# p6_wch_link.net
KiCad netlist of a schematic drawn in Altium Designer
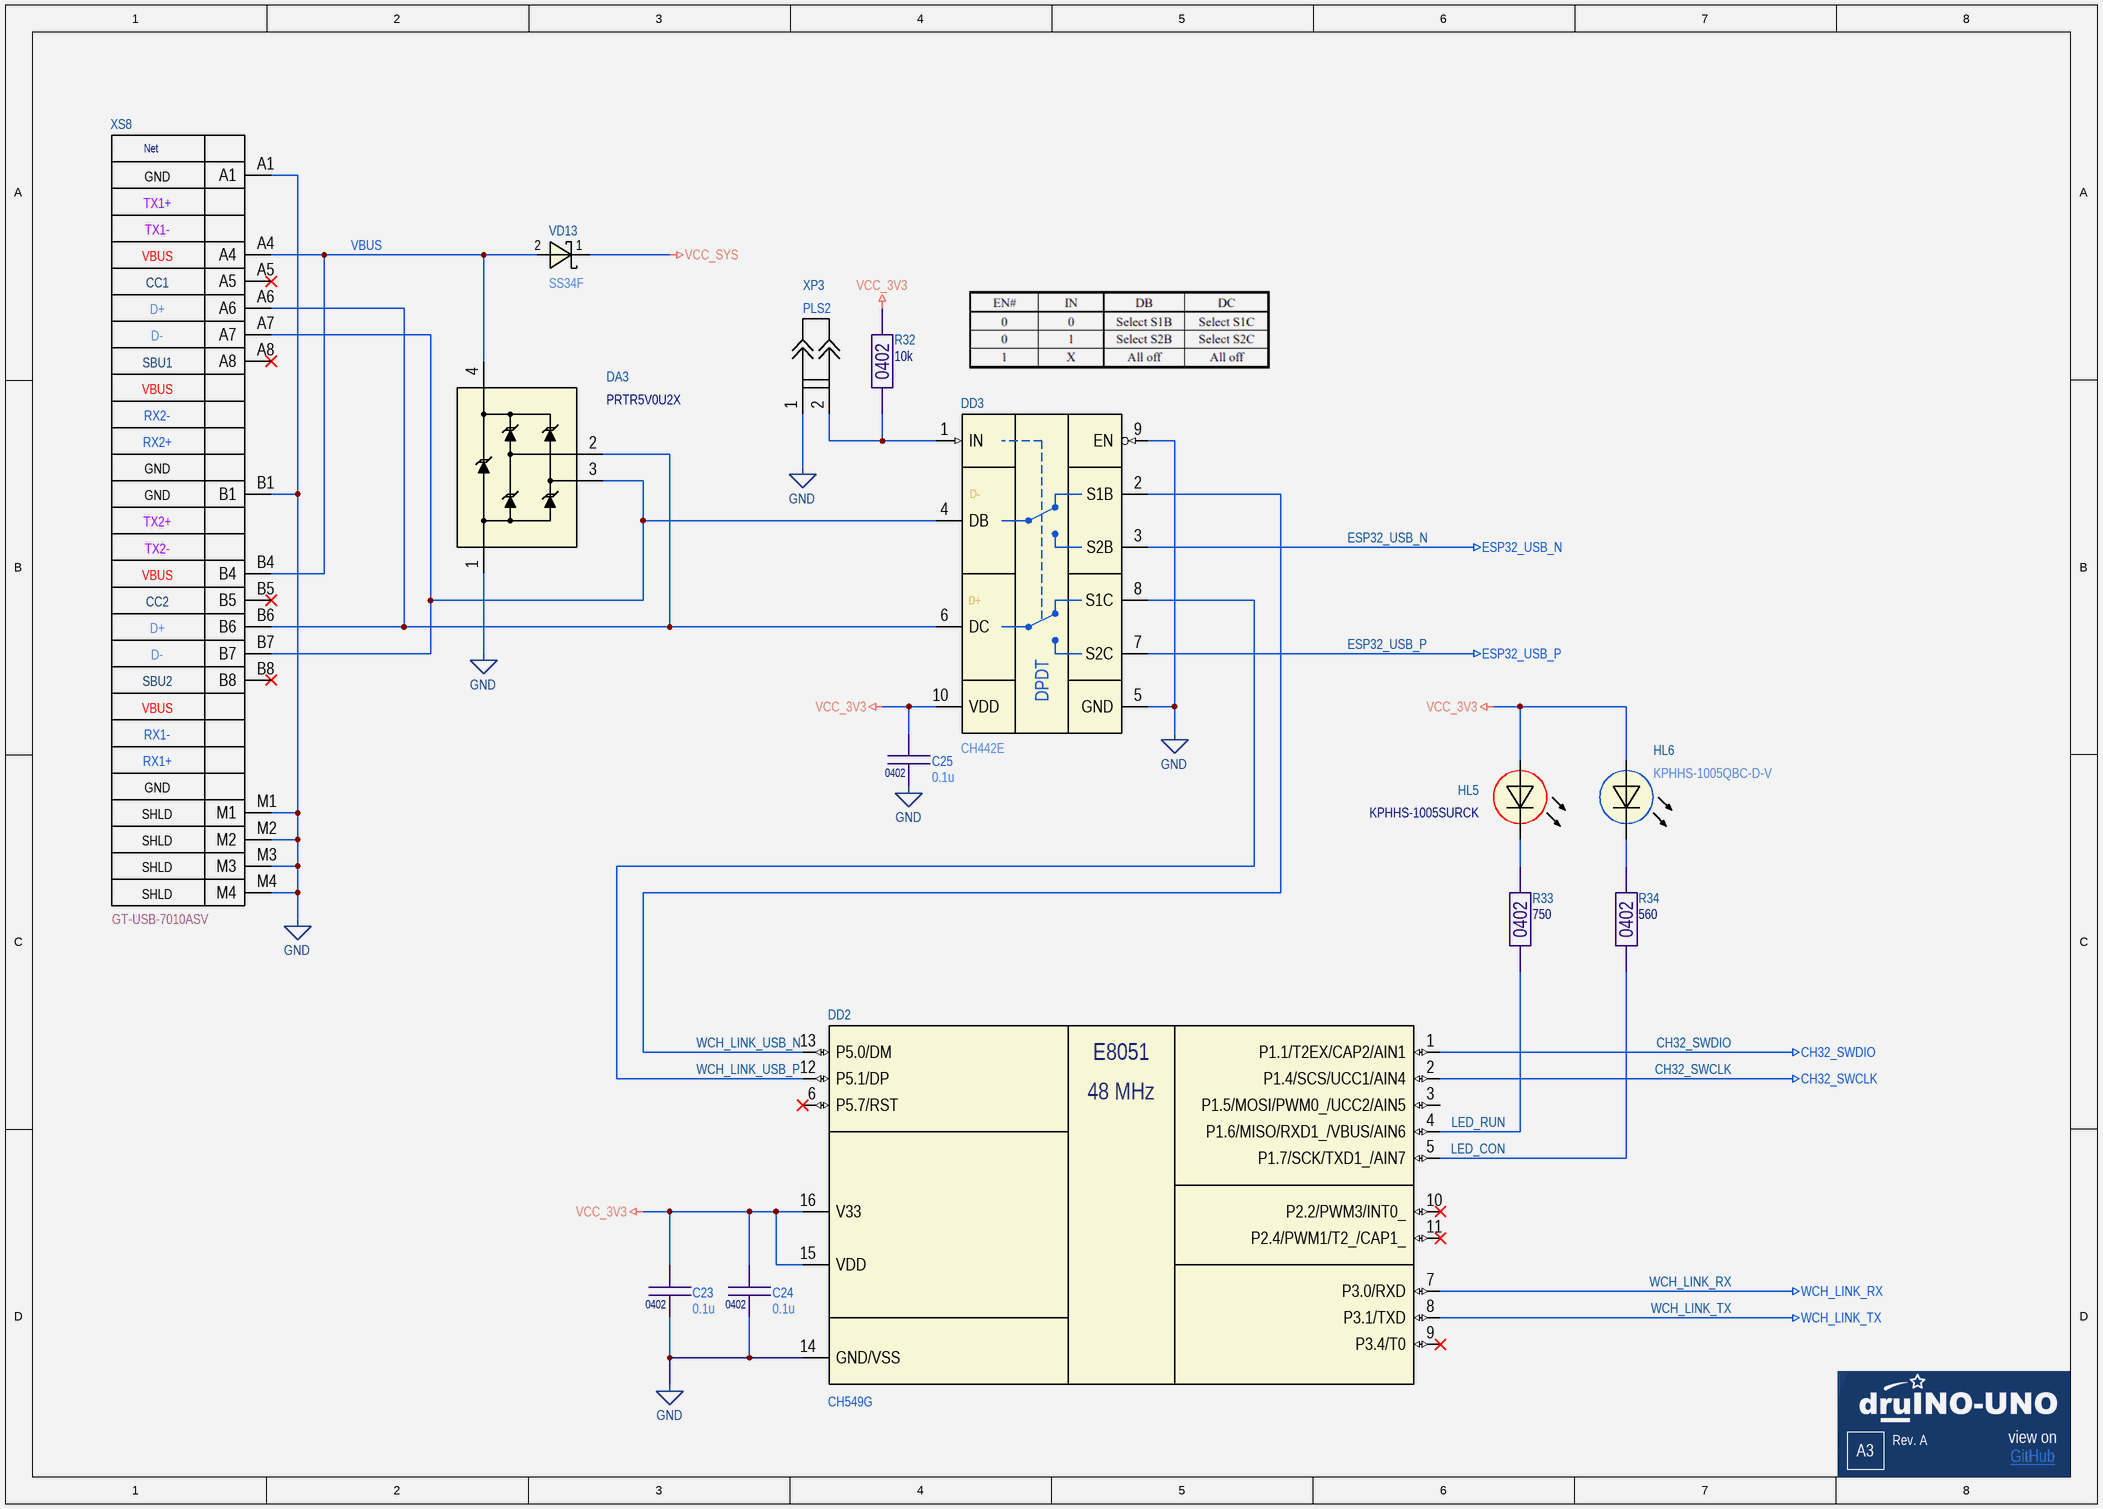
[diagram p0: p6_wch_link.SchDoc]

(export (version "E")
  (design (tool "Eeschema 10.0.6"))
  (components
    (comp (ref "C23")
      (value "0.1u")
      (footprint "PcbLib_RC:CAP0402")
      (description "Capacitors 0402 package case")
      (fields
        (field (name "TOLERANCE") "± 5 %")
        (field (name "VOLTAGE") "50 V")
        (field (name "PACKAGE") "0402")
      )
      (libsource (lib "Schlib_RC") (part "C0402"))
    )
    (comp (ref "C24")
      (value "0.1u")
      (footprint "PcbLib_RC:CAP0402")
      (description "Capacitors 0402 package case")
      (fields
        (field (name "TOLERANCE") "± 5 %")
        (field (name "VOLTAGE") "50 V")
        (field (name "PACKAGE") "0402")
      )
      (libsource (lib "Schlib_RC") (part "C0402"))
    )
    (comp (ref "C25")
      (value "0.1u")
      (footprint "PcbLib_RC:CAP0402")
      (description "Capacitors 0402 package case")
      (fields
        (field (name "TOLERANCE") "± 5 %")
        (field (name "VOLTAGE") "50 V")
        (field (name "PACKAGE") "0402")
      )
      (libsource (lib "Schlib_RC") (part "C0402"))
    )
    (comp (ref "DA3")
      (value "PRTR5V0U2X")
      (footprint "PcbLib_ICs:SOT143")
      (description "Ultra low capacitance double rail-to-rail ESD protection diode")
      (fields (field (name "MANUFACTURER") "NXP USA Inc."))
      (libsource (lib "Schlib_NXP_Semiconductors") (part "PRTR5V0U2X"))
    )
    (comp (ref "DD2")
      (value "CH549G")
      (footprint "PcbLib_ICs:SOIC-16")
      (description "8-bit Enhanced USB MCU")
      (fields (field (name "MANUFACTURER") "WinChipHead"))
      (libsource (lib "Schlib_WCH") (part "CH549G"))
    )
    (comp (ref "DD3")
      (value "CH442E")
      (footprint "PcbLib_ICs:MSOP-10")
      (description "Double-pole Double-throw Low-Resistance Analog Switch IC")
      (fields (field (name "MANUFACTURER") "WinChipHead"))
      (libsource (lib "Schlib_WCH") (part "CH442E"))
    )
    (comp (ref "HL5")
      (value "KPHHS-1005SURCK")
      (footprint "PcbLib_Others:LED0402R")
      (description "Red led (package case 0402)")
      (fields (field (name "MANUFACTURER") "Kingbright Company LLC."))
      (libsource (lib "Schlib_Kingbright") (part "KPHHS-1005SURCK"))
    )
    (comp (ref "HL6")
      (value "KPHHS-1005QBC-D-V")
      (footprint "PcbLib_Others:LED0402B")
      (description "Blue led (package case 0402)")
      (fields (field (name "MANUFACTURER") "Kingbright Company LLC."))
      (libsource (lib "Schlib_Kingbright") (part "KPHHS-1005QBC-D-V"))
    )
    (comp (ref "R32")
      (value "10k")
      (footprint "PcbLib_RC:RES0402B")
      (description "Resistor 0402 package case")
      (fields
        (field (name "TOLERANCE") "± 1 %")
        (field (name "PART NUMBER") "RC0402FR-0710KL")
        (field (name "PACKAGE") "0402")
      )
      (libsource (lib "Schlib_RC") (part "R0402"))
    )
    (comp (ref "R33")
      (value "750")
      (footprint "PcbLib_RC:RES0402B")
      (description "Resistor 0402 package case")
      (fields
        (field (name "TOLERANCE") "± 1 %")
        (field (name "PART NUMBER") "RC0402FR-07750RL")
        (field (name "PACKAGE") "0402")
      )
      (libsource (lib "Schlib_RC") (part "R0402"))
    )
    (comp (ref "R34")
      (value "560")
      (footprint "PcbLib_RC:RES0402B")
      (description "Resistor 0402 package case")
      (fields
        (field (name "TOLERANCE") "± 1 %")
        (field (name "PART NUMBER") "RC0402FR-07560RL")
        (field (name "PACKAGE") "0402")
      )
      (libsource (lib "Schlib_RC") (part "R0402"))
    )
    (comp (ref "VD13")
      (value "SS34F")
      (footprint "PcbLib_Discrete:SMA-FL")
      (description "3A Schottky barrier rectifier")
      (fields (field (name "MANUFACTURER") "UMW"))
      (libsource (lib "Schlib_UMW") (part "SS34F"))
    )
    (comp (ref "XP3")
      (value "PLS2")
      (footprint "PcbLib_Pin_Headers:PLS-2")
      (libsource (lib "Schlib_OtherComponents") (part "PLS2"))
    )
    (comp (ref "XS8")
      (value "GT-USB-7010ASV")
      (footprint "PcbLib_Connectors:GT-USB-7010ASV")
      (description "USB 2.0 Female 3A Surface 16P")
      (fields (field (name "MANUFACTURER") "G-Switch"))
      (libsource (lib "Schlib_OtherComponents") (part "GT-USB-7010ASV"))
    )
  )
  (nets
    (net (code "1") (name "/LED_CON") (class "Default")
      (node (ref "DD2") (pin "5") (pinfunction "P1.7/SCK/TXD1_/AIN7_5") (pintype "bidirectional"))
      (node (ref "R34") (pin "2") (pinfunction "2_2") (pintype "passive"))
    )
    (net (code "2") (name "/LED_RUN") (class "Default")
      (node (ref "DD2") (pin "4") (pinfunction "P1.6/MISO/RXD1_/VBUS/AIN6_4") (pintype "bidirectional"))
      (node (ref "R33") (pin "2") (pinfunction "2_2") (pintype "passive"))
    )
    (net (code "3") (name "/VBUS") (class "Default")
      (node (ref "DA3") (pin "4") (pinfunction "VCC_4") (pintype "passive"))
      (node (ref "VD13") (pin "2") (pinfunction "2_2") (pintype "passive"))
      (node (ref "XS8") (pin "A4") (pinfunction "A4_A4") (pintype "passive"))
      (node (ref "XS8") (pin "B4") (pinfunction "B4_B4") (pintype "passive"))
    )
    (net (code "4") (name "/WCH_LINK_USB_N") (class "Default")
      (node (ref "DD2") (pin "13") (pinfunction "P5.0/DM_13") (pintype "bidirectional"))
      (node (ref "DD3") (pin "2") (pinfunction "S1B_2") (pintype "passive"))
    )
    (net (code "5") (name "/WCH_LINK_USB_P") (class "Default")
      (node (ref "DD2") (pin "12") (pinfunction "P5.1/DP_12") (pintype "bidirectional"))
      (node (ref "DD3") (pin "8") (pinfunction "S1C_8") (pintype "passive"))
    )
    (net (code "6") (name "CH32_SWCLK") (class "Default")
      (node (ref "DD2") (pin "2") (pinfunction "P1.4/SCS/UCC1/AIN4_2") (pintype "bidirectional"))
    )
    (net (code "7") (name "CH32_SWDIO") (class "Default")
      (node (ref "DD2") (pin "1") (pinfunction "P1.1/T2EX/CAP2/AIN1_1") (pintype "bidirectional"))
    )
    (net (code "8") (name "ESP32_USB_N") (class "Default")
      (node (ref "DD3") (pin "3") (pinfunction "S2B_3") (pintype "passive"))
    )
    (net (code "9") (name "ESP32_USB_P") (class "Default")
      (node (ref "DD3") (pin "7") (pinfunction "S2C_7") (pintype "passive"))
    )
    (net (code "10") (name "GND") (class "Default")
      (node (ref "C23") (pin "2") (pinfunction "2_2") (pintype "passive"))
      (node (ref "C24") (pin "2") (pinfunction "2_2") (pintype "passive"))
      (node (ref "C25") (pin "2") (pinfunction "2_2") (pintype "passive"))
      (node (ref "DA3") (pin "1") (pinfunction "GND_1") (pintype "passive"))
      (node (ref "DD2") (pin "14") (pinfunction "GND/VSS_14") (pintype "power_in"))
      (node (ref "DD3") (pin "5") (pinfunction "GND_5") (pintype "power_in"))
      (node (ref "DD3") (pin "9") (pinfunction "EN_9") (pintype "input"))
      (node (ref "XP3") (pin "1") (pinfunction "1_1") (pintype "passive"))
      (node (ref "XS8") (pin "A1") (pinfunction "A1_A1") (pintype "passive"))
      (node (ref "XS8") (pin "B1") (pinfunction "B1_B1") (pintype "passive"))
      (node (ref "XS8") (pin "M1") (pinfunction "M1_M1") (pintype "passive"))
      (node (ref "XS8") (pin "M2") (pinfunction "M2_M2") (pintype "passive"))
      (node (ref "XS8") (pin "M3") (pinfunction "M3_M3") (pintype "passive"))
      (node (ref "XS8") (pin "M4") (pinfunction "M4_M4") (pintype "passive"))
    )
    (net (code "11") (name "Net-(DA3-IO1)") (class "Default")
      (node (ref "DA3") (pin "2") (pinfunction "IO1_2") (pintype "passive"))
      (node (ref "DD3") (pin "6") (pinfunction "DC_6") (pintype "passive"))
      (node (ref "XS8") (pin "A6") (pinfunction "A6_A6") (pintype "passive"))
      (node (ref "XS8") (pin "B6") (pinfunction "B6_B6") (pintype "passive"))
    )
    (net (code "12") (name "Net-(DA3-IO2)") (class "Default")
      (node (ref "DA3") (pin "3") (pinfunction "IO2_3") (pintype "passive"))
      (node (ref "DD3") (pin "4") (pinfunction "DB_4") (pintype "passive"))
      (node (ref "XS8") (pin "A7") (pinfunction "A7_A7") (pintype "passive"))
      (node (ref "XS8") (pin "B7") (pinfunction "B7_B7") (pintype "passive"))
    )
    (net (code "13") (name "Net-(DD3-IN)") (class "Default")
      (node (ref "DD3") (pin "1") (pinfunction "IN_1") (pintype "input"))
      (node (ref "R32") (pin "2") (pinfunction "2_2") (pintype "passive"))
      (node (ref "XP3") (pin "2") (pinfunction "2_2") (pintype "passive"))
    )
    (net (code "14") (name "Net-(HL5-Pad1)") (class "Default")
      (node (ref "HL5") (pin "1") (pinfunction "1_1") (pintype "passive"))
      (node (ref "R33") (pin "1") (pinfunction "1_1") (pintype "passive"))
    )
    (net (code "15") (name "Net-(HL6-Pad1)") (class "Default")
      (node (ref "HL6") (pin "1") (pinfunction "1_1") (pintype "passive"))
      (node (ref "R34") (pin "1") (pinfunction "1_1") (pintype "passive"))
    )
    (net (code "16") (name "VCC_3V3") (class "Default")
      (node (ref "C23") (pin "1") (pinfunction "1_1") (pintype "passive"))
      (node (ref "C24") (pin "1") (pinfunction "1_1") (pintype "passive"))
      (node (ref "C25") (pin "1") (pinfunction "1_1") (pintype "passive"))
      (node (ref "DD2") (pin "15") (pinfunction "VDD_15") (pintype "power_in"))
      (node (ref "DD2") (pin "16") (pinfunction "V33_16") (pintype "power_in"))
      (node (ref "DD3") (pin "10") (pinfunction "VDD_10") (pintype "power_in"))
      (node (ref "HL5") (pin "2") (pinfunction "2_2") (pintype "passive"))
      (node (ref "HL6") (pin "2") (pinfunction "2_2") (pintype "passive"))
      (node (ref "R32") (pin "1") (pinfunction "1_1") (pintype "passive"))
    )
    (net (code "17") (name "VCC_SYS") (class "Default")
      (node (ref "VD13") (pin "1") (pinfunction "1_1") (pintype "passive"))
    )
    (net (code "18") (name "WCH_LINK_RX") (class "Default")
      (node (ref "DD2") (pin "7") (pinfunction "P3.0/RXD_7") (pintype "bidirectional"))
    )
    (net (code "19") (name "WCH_LINK_TX") (class "Default")
      (node (ref "DD2") (pin "8") (pinfunction "P3.1/TXD_8") (pintype "bidirectional"))
    )
    (net (code "20") (name "unconnected-(DD2-P1.5{slash}MOSI{slash}PWM0_{slash}UCC2{slash}AIN5-Pad3)") (class "Default")
      (node (ref "DD2") (pin "3") (pinfunction "P1.5/MOSI/PWM0_/UCC2/AIN5_3") (pintype "bidirectional"))
    )
    (net (code "21") (name "unconnected-(DD2-P2.2{slash}PWM3{slash}INT0_-Pad10)") (class "Default")
      (node (ref "DD2") (pin "10") (pinfunction "P2.2/PWM3/INT0__10") (pintype "bidirectional+no_connect"))
    )
    (net (code "22") (name "unconnected-(DD2-P2.4{slash}PWM1{slash}T2_{slash}CAP1_-Pad11)") (class "Default")
      (node (ref "DD2") (pin "11") (pinfunction "P2.4/PWM1/T2_/CAP1__11") (pintype "bidirectional+no_connect"))
    )
    (net (code "23") (name "unconnected-(DD2-P3.4{slash}T0-Pad9)") (class "Default")
      (node (ref "DD2") (pin "9") (pinfunction "P3.4/T0_9") (pintype "bidirectional+no_connect"))
    )
    (net (code "24") (name "unconnected-(DD2-P5.7{slash}RST-Pad6)") (class "Default")
      (node (ref "DD2") (pin "6") (pinfunction "P5.7/RST_6") (pintype "bidirectional+no_connect"))
    )
    (net (code "25") (name "unconnected-(XS8-PadA5)") (class "Default")
      (node (ref "XS8") (pin "A5") (pinfunction "A5_A5") (pintype "passive+no_connect"))
    )
    (net (code "26") (name "unconnected-(XS8-PadA8)") (class "Default")
      (node (ref "XS8") (pin "A8") (pinfunction "A8_A8") (pintype "passive+no_connect"))
    )
    (net (code "27") (name "unconnected-(XS8-PadB5)") (class "Default")
      (node (ref "XS8") (pin "B5") (pinfunction "B5_B5") (pintype "passive+no_connect"))
    )
    (net (code "28") (name "unconnected-(XS8-PadB8)") (class "Default")
      (node (ref "XS8") (pin "B8") (pinfunction "B8_B8") (pintype "passive+no_connect"))
    )
  )
)
